# sterownik.net
KiCad netlist of a schematic drawn in Altium Designer
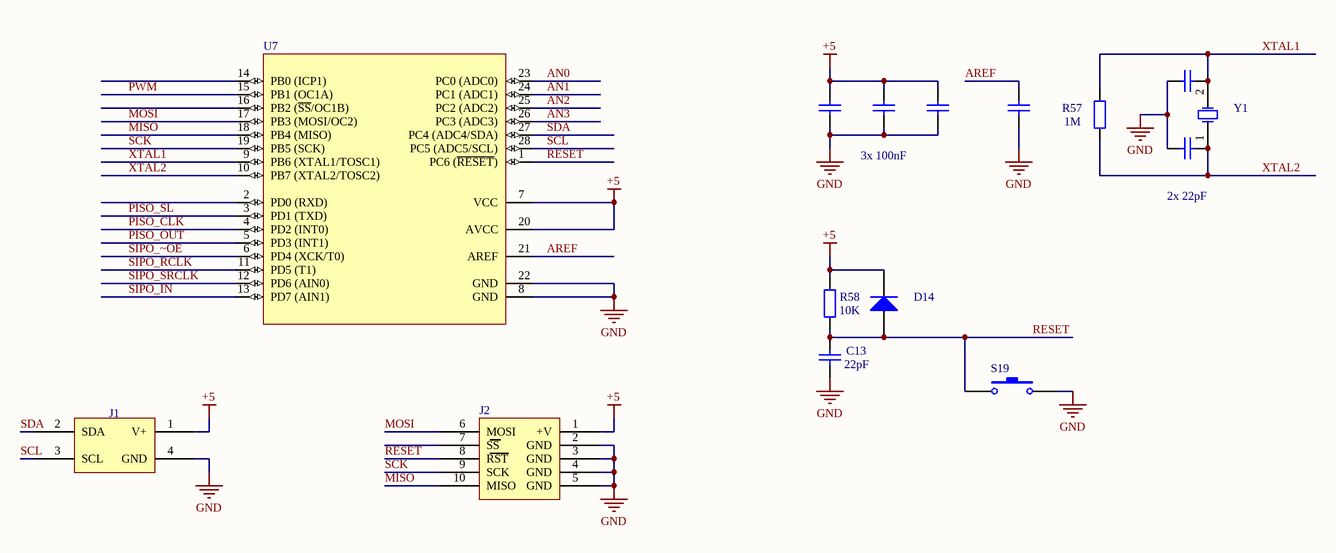
[diagram p0: sterownik.SchDoc]

(export (version "E")
  (design (tool "Eeschema 10.0.6"))
  (components
    (comp (ref "C7")
      (value "http://www.tme.eu/pl/details/12061c104kat2a/kondensatory-mlcc-smd-1206/avx/")
      (footprint "C1206")
      (description "100nF")
      (fields (field (name "PUBLISHER") "Altium Limited"))
      (libsource (lib "Miscellaneous Devices") (part "Cap"))
    )
    (comp (ref "C8")
      (value "http://www.tme.eu/pl/details/12061c104kat2a/kondensatory-mlcc-smd-1206/avx/")
      (footprint "C1206")
      (description "100nF")
      (fields (field (name "PUBLISHER") "Altium Limited"))
      (libsource (lib "Miscellaneous Devices") (part "Cap"))
    )
    (comp (ref "C9")
      (value "http://www.tme.eu/pl/details/12061c104kat2a/kondensatory-mlcc-smd-1206/avx/")
      (footprint "C1206")
      (description "100nF")
      (fields (field (name "PUBLISHER") "Altium Limited"))
      (libsource (lib "Miscellaneous Devices") (part "Cap"))
    )
    (comp (ref "C10")
      (value "http://www.tme.eu/pl/details/12061c104kat2a/kondensatory-mlcc-smd-1206/avx/")
      (footprint "C1206")
      (description "100nF")
      (fields (field (name "PUBLISHER") "Altium Limited"))
      (libsource (lib "Miscellaneous Devices") (part "Cap"))
    )
    (comp (ref "C11")
      (value "http://www.tme.eu/pl/details/cl31c220jbcnnnc/kondensatory-mlcc-smd-1206/samsung/")
      (footprint "C1206")
      (description "22pF")
      (fields (field (name "PUBLISHER") "Altium Limited"))
      (libsource (lib "Miscellaneous Devices") (part "Cap"))
    )
    (comp (ref "C12")
      (value "http://www.tme.eu/pl/details/cl31c220jbcnnnc/kondensatory-mlcc-smd-1206/samsung/")
      (footprint "C1206")
      (description "22pF")
      (fields (field (name "PUBLISHER") "Altium Limited"))
      (libsource (lib "Miscellaneous Devices") (part "Cap"))
    )
    (comp (ref "C13")
      (value "22pF")
      (footprint "C1206")
      (fields
        (field (name "Comment") "http://www.tme.eu/pl/details/cl31c220jbcnnnc/kondensatory-mlcc-smd-1206/samsung/")
        (field (name "PUBLISHER") "Altium Limited")
      )
      (libsource (lib "Miscellaneous Devices") (part "Cap"))
    )
    (comp (ref "D14")
      (value "http://www.tme.eu/pl/details/1n4148-1206/diody-uniwersalne-smd/dc-components/cd4148w1206c/")
      (footprint "DIODA 1N4148")
      (description "Dioda 1N4148")
      (fields (field (name "PUBLISHER") "Altium Limited"))
      (libsource (lib "Miscellaneous Devices") (part "Diode 1N4148"))
    )
    (comp (ref "J1")
      (value "http://www.tme.eu/pl/details/p1304/zlacza-idc/tomic/")
      (footprint "IDC 4PIN")
      (description "Gniazdo IDC 4PIN")
      (libsource (lib "connectors") (part "i2c"))
    )
    (comp (ref "J2")
      (value "http://www.tme.eu/pl/details/09185106324/zlacza-idc/harting/")
      (footprint "IDC 10PIN")
      (description "Gniazdo IDC 10PIN")
      (libsource (lib "connectors") (part "SPI"))
    )
    (comp (ref "R57")
      (value "1M")
      (footprint "C1206")
      (fields
        (field (name "Comment") "http://www.tme.eu/pl/details/rc1206fr-071m/rezystory-smd-1206/yageo/rc1206fr-071ml/")
        (field (name "PUBLISHER") "Altium Limited")
      )
      (libsource (lib "Miscellaneous Devices") (part "Res2"))
    )
    (comp (ref "R58")
      (value "10K")
      (footprint "C1206")
      (fields
        (field (name "Comment") "http://www.tme.eu/pl/details/crcw120610k0jntabc/rezystory-smd-1206/vishay/")
        (field (name "PUBLISHER") "Altium Limited")
      )
      (libsource (lib "Miscellaneous Devices") (part "Res2"))
    )
    (comp (ref "S19")
      (value "http://www.tme.eu/pl/details/1301.9315/mikroprzelaczniki-tact-pcb/schurter/")
      (footprint "Microswitch_SMD")
      (description "Microswitch (SPST)")
      (fields (field (name "PUBLISHER") "Altium Limited"))
      (libsource (lib "Miscellaneous Devices") (part "SW-PB"))
    )
    (comp (ref "U7")
      (value "http://www.tme.eu/pl/details/atmega8a-au/mikrokontrolery-atmel-avr-smd/atmel/")
      (footprint "32A_N")
      (description "Atmega 8A-PU")
      (libsource (lib "Atmel Microcontroller megaAVR") (part "ATmega8A-PU"))
    )
    (comp (ref "Y1")
      (value "http://www.tme.eu/pl/details/16.00m-smdhc49s-ht/rezonatory-kwarcowe-smd/yic/16mhz-_105c-49smd-on-tape/")
      (footprint "crystal")
      (description "Kwarc 16MHz")
      (fields (field (name "PUBLISHER") "Altium Limited"))
      (libsource (lib "Miscellaneous Devices") (part "XTAL"))
    )
  )
  (nets
    (net (code "1") (name "+5") (class "Default")
      (node (ref "C7") (pin "2") (pinfunction "2_2") (pintype "passive"))
      (node (ref "C8") (pin "2") (pinfunction "2_2") (pintype "passive"))
      (node (ref "C9") (pin "2") (pinfunction "2_2") (pintype "passive"))
      (node (ref "D14") (pin "2") (pinfunction "K_2") (pintype "passive"))
      (node (ref "J1") (pin "1") (pinfunction "V+_1") (pintype "passive"))
      (node (ref "J2") (pin "1") (pinfunction "+V_1") (pintype "passive"))
      (node (ref "R58") (pin "2") (pinfunction "2_2") (pintype "passive"))
      (node (ref "U7") (pin "20") (pinfunction "AVCC_20") (pintype "power_in"))
      (node (ref "U7") (pin "7") (pinfunction "VCC_7") (pintype "power_in"))
    )
    (net (code "2") (name "/AN0") (class "Default")
      (node (ref "U7") (pin "23") (pinfunction "PC0_(ADC0)_23") (pintype "bidirectional"))
    )
    (net (code "3") (name "/AN1") (class "Default")
      (node (ref "U7") (pin "24") (pinfunction "PC1_(ADC1)_24") (pintype "bidirectional"))
    )
    (net (code "4") (name "/AN2") (class "Default")
      (node (ref "U7") (pin "25") (pinfunction "PC2_(ADC2)_25") (pintype "bidirectional"))
    )
    (net (code "5") (name "/AN3") (class "Default")
      (node (ref "U7") (pin "26") (pinfunction "PC3_(ADC3)_26") (pintype "bidirectional"))
    )
    (net (code "6") (name "/AREF") (class "Default")
      (node (ref "C10") (pin "1") (pinfunction "1_1") (pintype "passive"))
      (node (ref "U7") (pin "21") (pinfunction "AREF_21") (pintype "passive"))
    )
    (net (code "7") (name "/MISO") (class "Default")
      (node (ref "J2") (pin "10") (pinfunction "MISO_10") (pintype "passive"))
      (node (ref "U7") (pin "18") (pinfunction "PB4_(MISO)_18") (pintype "bidirectional"))
    )
    (net (code "8") (name "/MOSI") (class "Default")
      (node (ref "J2") (pin "6") (pinfunction "MOSI_6") (pintype "passive"))
      (node (ref "U7") (pin "17") (pinfunction "PB3_(MOSI/OC2)_17") (pintype "bidirectional"))
    )
    (net (code "9") (name "/PISO_CLK") (class "Default")
      (node (ref "U7") (pin "4") (pinfunction "PD2_(INT0)_4") (pintype "bidirectional"))
    )
    (net (code "10") (name "/PISO_OUT") (class "Default")
      (node (ref "U7") (pin "5") (pinfunction "PD3_(INT1)_5") (pintype "bidirectional"))
    )
    (net (code "11") (name "/PISO_SL") (class "Default")
      (node (ref "U7") (pin "3") (pinfunction "PD1_(TXD)_3") (pintype "bidirectional"))
    )
    (net (code "12") (name "/PWM") (class "Default")
      (node (ref "U7") (pin "15") (pinfunction "PB1_(OC1A)_15") (pintype "bidirectional"))
    )
    (net (code "13") (name "/RESET") (class "Default")
      (node (ref "C13") (pin "2") (pinfunction "2_2") (pintype "passive"))
      (node (ref "D14") (pin "1") (pinfunction "A_1") (pintype "passive"))
      (node (ref "J2") (pin "8") (pinfunction "RST_8") (pintype "passive"))
      (node (ref "R58") (pin "1") (pinfunction "1_1") (pintype "passive"))
      (node (ref "S19") (pin "1") (pinfunction "1_1") (pintype "passive"))
      (node (ref "U7") (pin "1") (pinfunction "PC6_(~{RESET})_1") (pintype "bidirectional"))
    )
    (net (code "14") (name "/SCK") (class "Default")
      (node (ref "J2") (pin "9") (pinfunction "SCK_9") (pintype "passive"))
      (node (ref "U7") (pin "19") (pinfunction "PB5_(SCK)_19") (pintype "bidirectional"))
    )
    (net (code "15") (name "/SCL") (class "Default")
      (node (ref "J1") (pin "3") (pinfunction "SCL_3") (pintype "passive"))
      (node (ref "U7") (pin "28") (pinfunction "PC5_(ADC5/SCL)_28") (pintype "bidirectional"))
    )
    (net (code "16") (name "/SDA") (class "Default")
      (node (ref "J1") (pin "2") (pinfunction "SDA_2") (pintype "passive"))
      (node (ref "U7") (pin "27") (pinfunction "PC4_(ADC4/SDA)_27") (pintype "bidirectional"))
    )
    (net (code "17") (name "/SIPO_IN") (class "Default")
      (node (ref "U7") (pin "13") (pinfunction "PD7_(AIN1)_13") (pintype "bidirectional"))
    )
    (net (code "18") (name "/SIPO_RCLK") (class "Default")
      (node (ref "U7") (pin "11") (pinfunction "PD5_(T1)_11") (pintype "bidirectional"))
    )
    (net (code "19") (name "/SIPO_SRCLK") (class "Default")
      (node (ref "U7") (pin "12") (pinfunction "PD6_(AIN0)_12") (pintype "bidirectional"))
    )
    (net (code "20") (name "/SIPO_~OE") (class "Default")
      (node (ref "U7") (pin "6") (pinfunction "PD4_(XCK/T0)_6") (pintype "bidirectional"))
    )
    (net (code "21") (name "/XTAL1") (class "Default")
      (node (ref "C11") (pin "2") (pinfunction "2_2") (pintype "passive"))
      (node (ref "R57") (pin "2") (pinfunction "2_2") (pintype "passive"))
      (node (ref "U7") (pin "9") (pinfunction "PB6_(XTAL1/TOSC1)_9") (pintype "bidirectional"))
      (node (ref "Y1") (pin "2") (pinfunction "OSC2_2") (pintype "passive"))
    )
    (net (code "22") (name "/XTAL2") (class "Default")
      (node (ref "C12") (pin "2") (pinfunction "2_2") (pintype "passive"))
      (node (ref "R57") (pin "1") (pinfunction "1_1") (pintype "passive"))
      (node (ref "U7") (pin "10") (pinfunction "PB7_(XTAL2/TOSC2)_10") (pintype "bidirectional"))
      (node (ref "Y1") (pin "1") (pinfunction "OSC1_1") (pintype "passive"))
    )
    (net (code "23") (name "GND") (class "Default")
      (node (ref "C10") (pin "2") (pinfunction "2_2") (pintype "passive"))
      (node (ref "C11") (pin "1") (pinfunction "1_1") (pintype "passive"))
      (node (ref "C12") (pin "1") (pinfunction "1_1") (pintype "passive"))
      (node (ref "C13") (pin "1") (pinfunction "1_1") (pintype "passive"))
      (node (ref "C7") (pin "1") (pinfunction "1_1") (pintype "passive"))
      (node (ref "C8") (pin "1") (pinfunction "1_1") (pintype "passive"))
      (node (ref "C9") (pin "1") (pinfunction "1_1") (pintype "passive"))
      (node (ref "J1") (pin "4") (pinfunction "GND_4") (pintype "passive"))
      (node (ref "J2") (pin "2") (pinfunction "GND_2") (pintype "passive"))
      (node (ref "J2") (pin "3") (pinfunction "GND_3") (pintype "passive"))
      (node (ref "J2") (pin "4") (pinfunction "GND_4") (pintype "passive"))
      (node (ref "J2") (pin "5") (pinfunction "GND_5") (pintype "passive"))
      (node (ref "S19") (pin "2") (pinfunction "2_2") (pintype "passive"))
      (node (ref "U7") (pin "22") (pinfunction "GND_22") (pintype "power_in"))
      (node (ref "U7") (pin "8") (pinfunction "GND_8") (pintype "power_in"))
    )
    (net (code "24") (name "unconnected-(J2-SS-Pad7)") (class "Default")
      (node (ref "J2") (pin "7") (pinfunction "SS_7") (pintype "passive"))
    )
    (net (code "25") (name "unconnected-(U7-PB0_(ICP1)-Pad14)") (class "Default")
      (node (ref "U7") (pin "14") (pinfunction "PB0_(ICP1)_14") (pintype "bidirectional"))
    )
    (net (code "26") (name "unconnected-(U7-PB2_(~{SS}{slash}OC1B)-Pad16)") (class "Default")
      (node (ref "U7") (pin "16") (pinfunction "PB2_(~{SS}/OC1B)_16") (pintype "bidirectional"))
    )
    (net (code "27") (name "unconnected-(U7-PD0_(RXD)-Pad2)") (class "Default")
      (node (ref "U7") (pin "2") (pinfunction "PD0_(RXD)_2") (pintype "bidirectional"))
    )
  )
)
